# sch_CPU.net
KiCad netlist of a schematic drawn in Altium Designer
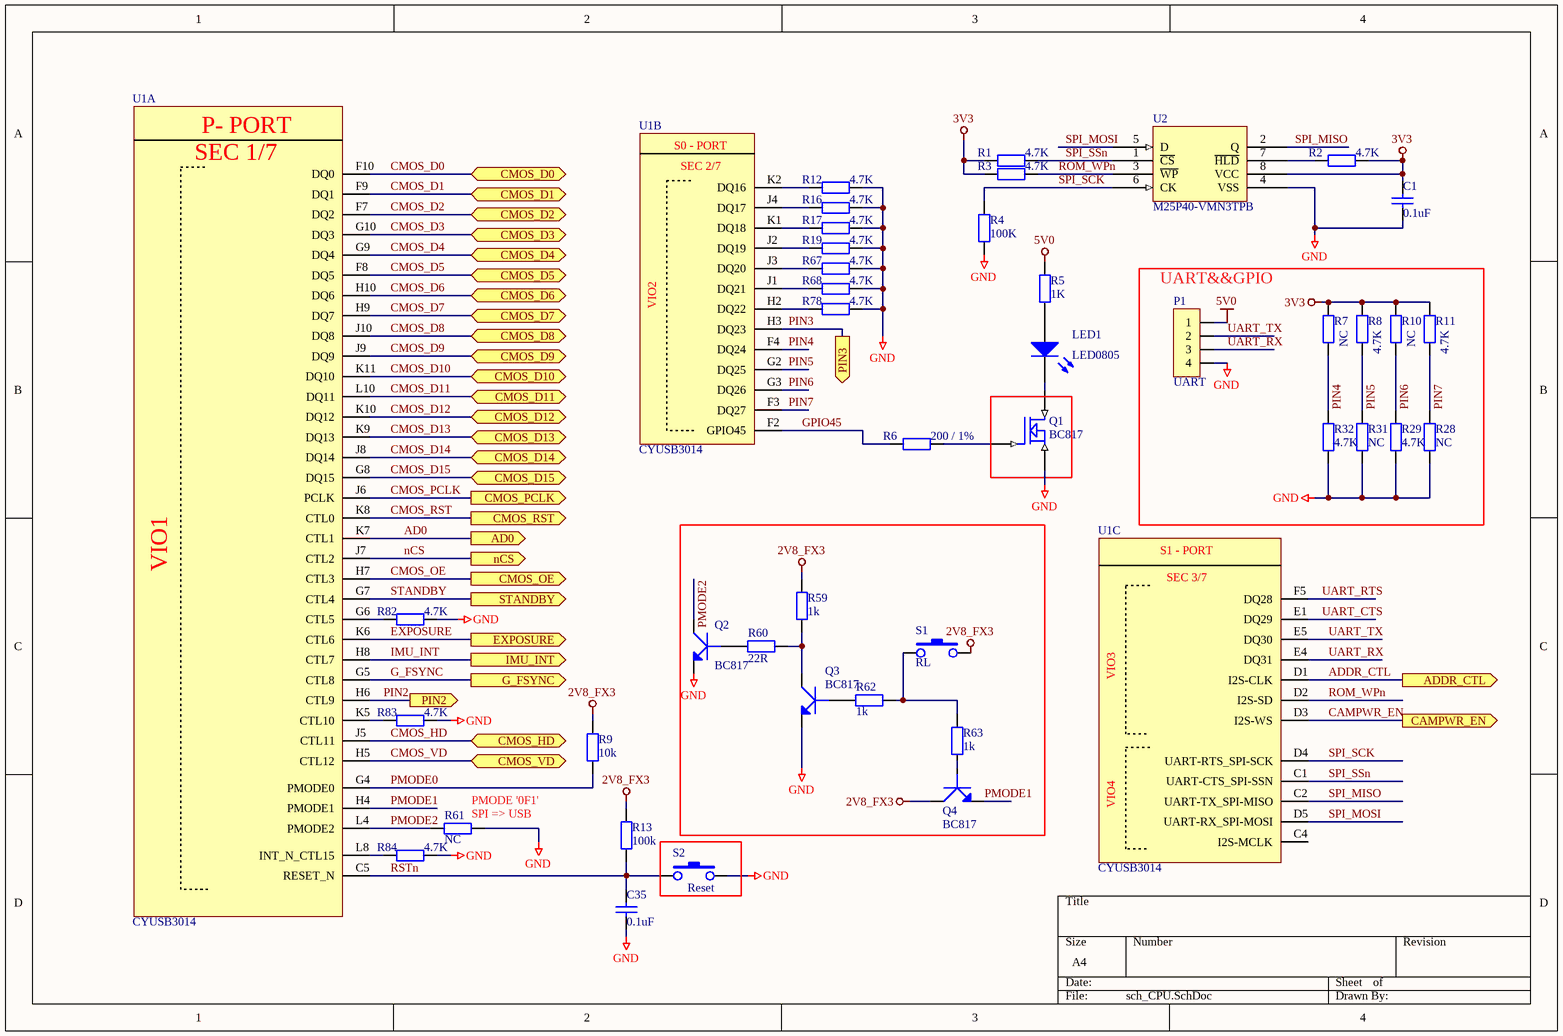
[diagram p0: sch_CPU.SchDoc]

(export (version "E")
  (design (tool "Eeschema 10.0.6"))
  (components
    (comp (ref "C1")
      (value "0.1uF")
      (footprint "0402C")
      (description "Capacitor")
      (fields (field (name "PUBLISHER") "Altium Limited"))
      (libsource (lib "Miscellaneous Devices") (part "Cap"))
    )
    (comp (ref "C35")
      (value "0.1uF")
      (footprint "0402C")
      (description "Capacitor")
      (fields (field (name "PUBLISHER") "Altium Limited"))
      (libsource (lib "Miscellaneous Devices") (part "Cap"))
    )
    (comp (ref "LED1")
      (value "LED0805")
      (footprint "LED0805A_L210W100H60")
      (description "发光二级管")
      (libsource (lib "TXW") (part "LED"))
    )
    (comp (ref "P1")
      (value "UART")
      (footprint "WAFER4_P1.25L6.25W3.4H4.3")
      (libsource (lib "KS_Drive") (part "CON4"))
    )
    (comp (ref "Q1")
      (value "BC817")
      (footprint "SOT-23L")
      (description "MOSFET N")
      (libsource (lib "TXW") (part "MOSFET N"))
    )
    (comp (ref "Q2")
      (value "BC817")
      (footprint "SOT-23L")
      (description "NPN Transistor")
      (libsource (lib "*") (part "NPN"))
    )
    (comp (ref "Q3")
      (value "BC817")
      (footprint "SOT-23L")
      (description "NPN Transistor")
      (libsource (lib "*") (part "NPN"))
    )
    (comp (ref "Q4")
      (value "BC817")
      (footprint "SOT-23L")
      (description "NPN Transistor")
      (libsource (lib "") (part "NPN_1"))
    )
    (comp (ref "R1")
      (value "4.7K")
      (footprint "0402R")
      (description "Resistor")
      (fields (field (name "PUBLISHER") "Altium Limited"))
      (libsource (lib "") (part "Resistor_2"))
    )
    (comp (ref "R2")
      (value "4.7K")
      (footprint "0402R")
      (description "Resistor")
      (fields (field (name "PUBLISHER") "Altium Limited"))
      (libsource (lib "") (part "Resistor_2"))
    )
    (comp (ref "R3")
      (value "4.7K")
      (footprint "0402R")
      (description "Resistor")
      (fields (field (name "PUBLISHER") "Altium Limited"))
      (libsource (lib "") (part "Resistor_2"))
    )
    (comp (ref "R4")
      (value "100K")
      (footprint "0402R")
      (description "Resistor")
      (fields (field (name "PUBLISHER") "Altium Limited"))
      (libsource (lib "") (part "Resistor_3"))
    )
    (comp (ref "R5")
      (value "1K")
      (footprint "0402R")
      (description "Resistor")
      (fields (field (name "PUBLISHER") "Altium Limited"))
      (libsource (lib "SZG") (part "Resistor"))
    )
    (comp (ref "R6")
      (value "200 / 1%")
      (footprint "0402R")
      (description "Resistor")
      (fields (field (name "Comment") "200R") (field (name "PUBLISHER") "Altium Limited"))
      (libsource (lib "") (part "Resistor_2"))
    )
    (comp (ref "R7")
      (value "NC")
      (footprint "0402R")
      (description "Resistor")
      (fields (field (name "PUBLISHER") "Altium Limited"))
      (libsource (lib "") (part "Resistor_3"))
    )
    (comp (ref "R8")
      (value "4.7K")
      (footprint "0402R")
      (description "Resistor")
      (fields (field (name "PUBLISHER") "Altium Limited"))
      (libsource (lib "") (part "Resistor_3"))
    )
    (comp (ref "R9")
      (value "10k")
      (footprint "0402R")
      (description "Resistor")
      (fields (field (name "Comment") "10K") (field (name "PUBLISHER") "Altium Limited"))
      (libsource (lib "SZG") (part "Resistor"))
    )
    (comp (ref "R10")
      (value "NC")
      (footprint "0402R")
      (description "Resistor")
      (fields (field (name "PUBLISHER") "Altium Limited"))
      (libsource (lib "") (part "Resistor_3"))
    )
    (comp (ref "R11")
      (value "4.7K")
      (footprint "0402R")
      (description "Resistor")
      (fields (field (name "PUBLISHER") "Altium Limited"))
      (libsource (lib "") (part "Resistor_3"))
    )
    (comp (ref "R12")
      (value "4.7K")
      (footprint "0402R")
      (description "Resistor")
      (fields (field (name "PUBLISHER") "Altium Limited"))
      (libsource (lib "") (part "Resistor_2"))
    )
    (comp (ref "R13")
      (value "100k")
      (footprint "0402R")
      (description "Resistor")
      (fields (field (name "Comment") "100K") (field (name "PUBLISHER") "Altium Limited"))
      (libsource (lib "SZG") (part "Resistor"))
    )
    (comp (ref "R16")
      (value "4.7K")
      (footprint "0402R")
      (description "Resistor")
      (fields (field (name "PUBLISHER") "Altium Limited"))
      (libsource (lib "") (part "Resistor_2"))
    )
    (comp (ref "R17")
      (value "4.7K")
      (footprint "0402R")
      (description "Resistor")
      (fields (field (name "PUBLISHER") "Altium Limited"))
      (libsource (lib "") (part "Resistor_2"))
    )
    (comp (ref "R19")
      (value "4.7K")
      (footprint "0402R")
      (description "Resistor")
      (fields (field (name "PUBLISHER") "Altium Limited"))
      (libsource (lib "") (part "Resistor_2"))
    )
    (comp (ref "R28")
      (value "NC")
      (footprint "0402R")
      (description "Resistor")
      (fields (field (name "PUBLISHER") "Altium Limited"))
      (libsource (lib "SZG") (part "Resistor"))
    )
    (comp (ref "R29")
      (value "4.7K")
      (footprint "0402R")
      (description "Resistor")
      (fields (field (name "PUBLISHER") "Altium Limited"))
      (libsource (lib "SZG") (part "Resistor"))
    )
    (comp (ref "R31")
      (value "NC")
      (footprint "0402R")
      (description "Resistor")
      (fields (field (name "Comment") "N~{C}") (field (name "PUBLISHER") "Altium Limited"))
      (libsource (lib "SZG") (part "Resistor"))
    )
    (comp (ref "R32")
      (value "4.7K")
      (footprint "0402R")
      (description "Resistor")
      (fields (field (name "PUBLISHER") "Altium Limited"))
      (libsource (lib "SZG") (part "Resistor"))
    )
    (comp (ref "R59")
      (value "1k")
      (footprint "0402R")
      (description "Resistor")
      (fields (field (name "Comment") "1K") (field (name "PUBLISHER") "Altium Limited"))
      (libsource (lib "") (part "Resistor_3"))
    )
    (comp (ref "R60")
      (value "22R")
      (footprint "0402R")
      (description "Resistor")
      (fields (field (name "PUBLISHER") "Altium Limited"))
      (libsource (lib "") (part "Resistor_2"))
    )
    (comp (ref "R61")
      (value "NC")
      (footprint "0805R")
      (description "Resistor")
      (fields (field (name "PUBLISHER") "Altium Limited"))
      (libsource (lib "") (part "Resistor_1"))
    )
    (comp (ref "R62")
      (value "1k")
      (footprint "0402R")
      (description "Resistor")
      (fields (field (name "PUBLISHER") "Altium Limited"))
      (libsource (lib "") (part "Resistor_1"))
    )
    (comp (ref "R63")
      (value "1k")
      (footprint "0402R")
      (description "Resistor")
      (fields (field (name "PUBLISHER") "Altium Limited"))
      (libsource (lib "SZG") (part "Resistor"))
    )
    (comp (ref "R67")
      (value "4.7K")
      (footprint "0402R")
      (description "Resistor")
      (fields (field (name "PUBLISHER") "Altium Limited"))
      (libsource (lib "") (part "Resistor_2"))
    )
    (comp (ref "R68")
      (value "4.7K")
      (footprint "0402R")
      (description "Resistor")
      (fields (field (name "PUBLISHER") "Altium Limited"))
      (libsource (lib "") (part "Resistor_2"))
    )
    (comp (ref "R78")
      (value "4.7K")
      (footprint "0402R")
      (description "Resistor")
      (fields (field (name "PUBLISHER") "Altium Limited"))
      (libsource (lib "") (part "Resistor_2"))
    )
    (comp (ref "R82")
      (value "4.7K")
      (footprint "0402R")
      (description "Resistor")
      (fields (field (name "PUBLISHER") "Altium Limited"))
      (libsource (lib "") (part "Resistor_2"))
    )
    (comp (ref "R83")
      (value "4.7K")
      (footprint "0402R")
      (description "Resistor")
      (fields (field (name "PUBLISHER") "Altium Limited"))
      (libsource (lib "") (part "Resistor_2"))
    )
    (comp (ref "R84")
      (value "4.7K")
      (footprint "0402R")
      (description "Resistor")
      (fields (field (name "PUBLISHER") "Altium Limited"))
      (libsource (lib "") (part "Resistor_2"))
    )
    (comp (ref "S1")
      (value "RL")
      (footprint "SW_L40W30H25_MPTFP")
      (description "Button_sop")
      (libsource (lib "SZG") (part "Button_sop"))
    )
    (comp (ref "S2")
      (value "Reset")
      (footprint "SW_L40W30H25_MPTFP")
      (description "Button_sop")
      (libsource (lib "SZG") (part "Button_sop"))
    )
    (comp (ref "U1")
      (value "CYUSB3014")
      (footprint "FBGA121_P80L100W100H11")
      (libsource (lib "TXW") (part "CYUSB3014"))
    )
    (comp (ref "U2")
      (value "M25P40-VMN3TPB")
      (footprint "SO8N_P127L50W40W62H17")
      (libsource (lib "TXW") (part "M25P40-VMN3TPB"))
    )
  )
  (nets
    (net (code "1") (name "/AD0") (class "Default")
      (node (ref "U1") (pin "K7") (pinfunction "CTL1_K7") (pintype "passive"))
    )
    (net (code "2") (name "/ADDR_CTL") (class "Default")
      (node (ref "U1") (pin "D1") (pinfunction "I2S-CLK_D1") (pintype "passive"))
    )
    (net (code "3") (name "/CAMPWR_EN") (class "Default")
      (node (ref "U1") (pin "D3") (pinfunction "I2S-WS_D3") (pintype "passive"))
    )
    (net (code "4") (name "/CMOS_D0") (class "Default")
      (node (ref "U1") (pin "F10") (pinfunction "DQ0_F10") (pintype "passive"))
    )
    (net (code "5") (name "/CMOS_D1") (class "Default")
      (node (ref "U1") (pin "F9") (pinfunction "DQ1_F9") (pintype "passive"))
    )
    (net (code "6") (name "/CMOS_D2") (class "Default")
      (node (ref "U1") (pin "F7") (pinfunction "DQ2_F7") (pintype "passive"))
    )
    (net (code "7") (name "/CMOS_D3") (class "Default")
      (node (ref "U1") (pin "G10") (pinfunction "DQ3_G10") (pintype "passive"))
    )
    (net (code "8") (name "/CMOS_D4") (class "Default")
      (node (ref "U1") (pin "G9") (pinfunction "DQ4_G9") (pintype "passive"))
    )
    (net (code "9") (name "/CMOS_D5") (class "Default")
      (node (ref "U1") (pin "F8") (pinfunction "DQ5_F8") (pintype "passive"))
    )
    (net (code "10") (name "/CMOS_D6") (class "Default")
      (node (ref "U1") (pin "H10") (pinfunction "DQ6_H10") (pintype "passive"))
    )
    (net (code "11") (name "/CMOS_D7") (class "Default")
      (node (ref "U1") (pin "H9") (pinfunction "DQ7_H9") (pintype "passive"))
    )
    (net (code "12") (name "/CMOS_D8") (class "Default")
      (node (ref "U1") (pin "J10") (pinfunction "DQ8_J10") (pintype "passive"))
    )
    (net (code "13") (name "/CMOS_D9") (class "Default")
      (node (ref "U1") (pin "J9") (pinfunction "DQ9_J9") (pintype "passive"))
    )
    (net (code "14") (name "/CMOS_D10") (class "Default")
      (node (ref "U1") (pin "K11") (pinfunction "DQ10_K11") (pintype "passive"))
    )
    (net (code "15") (name "/CMOS_D11") (class "Default")
      (node (ref "U1") (pin "L10") (pinfunction "DQ11_L10") (pintype "passive"))
    )
    (net (code "16") (name "/CMOS_D12") (class "Default")
      (node (ref "U1") (pin "K10") (pinfunction "DQ12_K10") (pintype "passive"))
    )
    (net (code "17") (name "/CMOS_D13") (class "Default")
      (node (ref "U1") (pin "K9") (pinfunction "DQ13_K9") (pintype "passive"))
    )
    (net (code "18") (name "/CMOS_D14") (class "Default")
      (node (ref "U1") (pin "J8") (pinfunction "DQ14_J8") (pintype "passive"))
    )
    (net (code "19") (name "/CMOS_D15") (class "Default")
      (node (ref "U1") (pin "G8") (pinfunction "DQ15_G8") (pintype "passive"))
    )
    (net (code "20") (name "/CMOS_HD") (class "Default")
      (node (ref "U1") (pin "J5") (pinfunction "CTL11_J5") (pintype "passive"))
    )
    (net (code "21") (name "/CMOS_OE") (class "Default")
      (node (ref "U1") (pin "H7") (pinfunction "CTL3_H7") (pintype "passive"))
    )
    (net (code "22") (name "/CMOS_PCLK") (class "Default")
      (node (ref "U1") (pin "J6") (pinfunction "PCLK_J6") (pintype "passive"))
    )
    (net (code "23") (name "/CMOS_RST") (class "Default")
      (node (ref "U1") (pin "K8") (pinfunction "CTL0_K8") (pintype "passive"))
    )
    (net (code "24") (name "/CMOS_VD") (class "Default")
      (node (ref "U1") (pin "H5") (pinfunction "CTL12_H5") (pintype "passive"))
    )
    (net (code "25") (name "/EXPOSURE") (class "Default")
      (node (ref "U1") (pin "K6") (pinfunction "CTL6_K6") (pintype "passive"))
    )
    (net (code "26") (name "/GPIO45") (class "Default")
      (node (ref "R6") (pin "1") (pinfunction "1_1") (pintype "passive"))
      (node (ref "U1") (pin "F2") (pinfunction "GPIO45_F2") (pintype "passive"))
    )
    (net (code "27") (name "/G_FSYNC") (class "Default")
      (node (ref "U1") (pin "G5") (pinfunction "CTL8_G5") (pintype "passive"))
    )
    (net (code "28") (name "/IMU_INT") (class "Default")
      (node (ref "U1") (pin "H8") (pinfunction "CTL7_H8") (pintype "passive"))
    )
    (net (code "29") (name "/PIN2") (class "Default")
      (node (ref "U1") (pin "H6") (pinfunction "CTL9_H6") (pintype "passive"))
    )
    (net (code "30") (name "/PIN3") (class "Default")
      (node (ref "U1") (pin "H3") (pinfunction "DQ23_H3") (pintype "passive"))
    )
    (net (code "31") (name "/PIN4") (class "Default")
      (node (ref "R32") (pin "1") (pinfunction "1_1") (pintype "passive"))
      (node (ref "R7") (pin "1") (pinfunction "1_1") (pintype "passive"))
      (node (ref "U1") (pin "F4") (pinfunction "DQ24_F4") (pintype "passive"))
    )
    (net (code "32") (name "/PIN5") (class "Default")
      (node (ref "R31") (pin "1") (pinfunction "1_1") (pintype "passive"))
      (node (ref "R8") (pin "1") (pinfunction "1_1") (pintype "passive"))
      (node (ref "U1") (pin "G2") (pinfunction "DQ25_G2") (pintype "passive"))
    )
    (net (code "33") (name "/PIN6") (class "Default")
      (node (ref "R10") (pin "1") (pinfunction "1_1") (pintype "passive"))
      (node (ref "R29") (pin "1") (pinfunction "1_1") (pintype "passive"))
      (node (ref "U1") (pin "G3") (pinfunction "DQ26_G3") (pintype "passive"))
    )
    (net (code "34") (name "/PIN7") (class "Default")
      (node (ref "R11") (pin "1") (pinfunction "1_1") (pintype "passive"))
      (node (ref "R28") (pin "1") (pinfunction "1_1") (pintype "passive"))
      (node (ref "U1") (pin "F3") (pinfunction "DQ27_F3") (pintype "passive"))
    )
    (net (code "35") (name "/PMODE0") (class "Default")
      (node (ref "R9") (pin "2") (pinfunction "2_2") (pintype "passive"))
      (node (ref "U1") (pin "G4") (pinfunction "PMODE0_G4") (pintype "passive"))
    )
    (net (code "36") (name "/PMODE1") (class "Default")
      (node (ref "Q4") (pin "2") (pinfunction "E_2") (pintype "passive"))
      (node (ref "U1") (pin "H4") (pinfunction "PMODE1_H4") (pintype "passive"))
    )
    (net (code "37") (name "/PMODE2") (class "Default")
      (node (ref "Q2") (pin "3") (pinfunction "C_3") (pintype "passive"))
      (node (ref "R61") (pin "2") (pinfunction "2_2") (pintype "passive"))
      (node (ref "U1") (pin "L4") (pinfunction "PMODE2_L4") (pintype "passive"))
    )
    (net (code "38") (name "/ROM_WPn") (class "Default")
      (node (ref "R3") (pin "2") (pinfunction "2_2") (pintype "passive"))
      (node (ref "U1") (pin "D2") (pinfunction "I2S-SD_D2") (pintype "passive"))
      (node (ref "U2") (pin "3") (pinfunction "~{WP}_3") (pintype "passive"))
    )
    (net (code "39") (name "/RSTn") (class "Default")
      (node (ref "C35") (pin "2") (pinfunction "2_2") (pintype "passive"))
      (node (ref "R13") (pin "2") (pinfunction "2_2") (pintype "passive"))
      (node (ref "S2") (pin "1") (pinfunction "1_1") (pintype "passive"))
      (node (ref "U1") (pin "C5") (pinfunction "RESET_N_C5") (pintype "passive"))
    )
    (net (code "40") (name "/SPI_MISO") (class "Default")
      (node (ref "U1") (pin "C2") (pinfunction "UART-TX_SPI-MISO_C2") (pintype "passive"))
      (node (ref "U2") (pin "2") (pinfunction "Q_2") (pintype "passive"))
    )
    (net (code "41") (name "/SPI_MOSI") (class "Default")
      (node (ref "U1") (pin "D5") (pinfunction "UART-RX_SPI-MOSI_D5") (pintype "passive"))
      (node (ref "U2") (pin "5") (pinfunction "D_5") (pintype "input"))
    )
    (net (code "42") (name "/SPI_SCK") (class "Default")
      (node (ref "R4") (pin "2") (pinfunction "2_2") (pintype "passive"))
      (node (ref "U1") (pin "D4") (pinfunction "UART-RTS_SPI-SCK_D4") (pintype "passive"))
      (node (ref "U2") (pin "6") (pinfunction "CK_6") (pintype "input"))
    )
    (net (code "43") (name "/SPI_SSn") (class "Default")
      (node (ref "R1") (pin "2") (pinfunction "2_2") (pintype "passive"))
      (node (ref "U1") (pin "C1") (pinfunction "UART-CTS_SPI-SSN_C1") (pintype "passive"))
      (node (ref "U2") (pin "1") (pinfunction "~{CS}_1") (pintype "passive"))
    )
    (net (code "44") (name "/STANDBY") (class "Default")
      (node (ref "U1") (pin "G7") (pinfunction "CTL4_G7") (pintype "passive"))
    )
    (net (code "45") (name "/UART_CTS") (class "Default")
      (node (ref "U1") (pin "E1") (pinfunction "DQ29_E1") (pintype "passive"))
    )
    (net (code "46") (name "/UART_RTS") (class "Default")
      (node (ref "U1") (pin "F5") (pinfunction "DQ28_F5") (pintype "passive"))
    )
    (net (code "47") (name "/UART_RX") (class "Default")
      (node (ref "P1") (pin "3") (pinfunction "3_3") (pintype "passive"))
      (node (ref "U1") (pin "E4") (pinfunction "DQ31_E4") (pintype "passive"))
    )
    (net (code "48") (name "/UART_TX") (class "Default")
      (node (ref "P1") (pin "2") (pinfunction "2_2") (pintype "passive"))
      (node (ref "U1") (pin "E5") (pinfunction "DQ30_E5") (pintype "passive"))
    )
    (net (code "49") (name "/nCS") (class "Default")
      (node (ref "U1") (pin "J7") (pinfunction "CTL2_J7") (pintype "passive"))
    )
    (net (code "50") (name "2V8_FX3") (class "Default")
      (node (ref "Q4") (pin "3") (pinfunction "C_3") (pintype "passive"))
      (node (ref "R13") (pin "1") (pinfunction "1_1") (pintype "passive"))
      (node (ref "R59") (pin "2") (pinfunction "2_2") (pintype "passive"))
      (node (ref "R9") (pin "1") (pinfunction "1_1") (pintype "passive"))
      (node (ref "S1") (pin "1") (pinfunction "1_1") (pintype "passive"))
    )
    (net (code "51") (name "3V3") (class "Default")
      (node (ref "C1") (pin "2") (pinfunction "2_2") (pintype "passive"))
      (node (ref "R1") (pin "1") (pinfunction "1_1") (pintype "passive"))
      (node (ref "R10") (pin "2") (pinfunction "2_2") (pintype "passive"))
      (node (ref "R11") (pin "2") (pinfunction "2_2") (pintype "passive"))
      (node (ref "R2") (pin "2") (pinfunction "2_2") (pintype "passive"))
      (node (ref "R3") (pin "1") (pinfunction "1_1") (pintype "passive"))
      (node (ref "R7") (pin "2") (pinfunction "2_2") (pintype "passive"))
      (node (ref "R8") (pin "2") (pinfunction "2_2") (pintype "passive"))
      (node (ref "U2") (pin "8") (pinfunction "VCC_8") (pintype "passive"))
    )
    (net (code "52") (name "5V0") (class "Default")
      (node (ref "P1") (pin "1") (pinfunction "1_1") (pintype "passive"))
      (node (ref "R5") (pin "1") (pinfunction "1_1") (pintype "passive"))
    )
    (net (code "53") (name "GND") (class "Default")
      (node (ref "C1") (pin "1") (pinfunction "1_1") (pintype "passive"))
      (node (ref "C35") (pin "1") (pinfunction "1_1") (pintype "passive"))
      (node (ref "P1") (pin "4") (pinfunction "4_4") (pintype "passive"))
      (node (ref "Q1") (pin "2") (pinfunction "S_2") (pintype "input"))
      (node (ref "Q2") (pin "2") (pinfunction "E_2") (pintype "passive"))
      (node (ref "Q3") (pin "2") (pinfunction "E_2") (pintype "passive"))
      (node (ref "R12") (pin "2") (pinfunction "2_2") (pintype "passive"))
      (node (ref "R16") (pin "2") (pinfunction "2_2") (pintype "passive"))
      (node (ref "R17") (pin "2") (pinfunction "2_2") (pintype "passive"))
      (node (ref "R19") (pin "2") (pinfunction "2_2") (pintype "passive"))
      (node (ref "R28") (pin "2") (pinfunction "2_2") (pintype "passive"))
      (node (ref "R29") (pin "2") (pinfunction "2_2") (pintype "passive"))
      (node (ref "R31") (pin "2") (pinfunction "2_2") (pintype "passive"))
      (node (ref "R32") (pin "2") (pinfunction "2_2") (pintype "passive"))
      (node (ref "R4") (pin "1") (pinfunction "1_1") (pintype "passive"))
      (node (ref "R61") (pin "1") (pinfunction "1_1") (pintype "passive"))
      (node (ref "R67") (pin "2") (pinfunction "2_2") (pintype "passive"))
      (node (ref "R68") (pin "2") (pinfunction "2_2") (pintype "passive"))
      (node (ref "R78") (pin "2") (pinfunction "2_2") (pintype "passive"))
      (node (ref "R82") (pin "2") (pinfunction "2_2") (pintype "passive"))
      (node (ref "R83") (pin "2") (pinfunction "2_2") (pintype "passive"))
      (node (ref "R84") (pin "2") (pinfunction "2_2") (pintype "passive"))
      (node (ref "S2") (pin "2") (pinfunction "2_2") (pintype "passive"))
      (node (ref "U2") (pin "4") (pinfunction "VSS_4") (pintype "passive"))
    )
    (net (code "54") (name "Net-(LED1-A)") (class "Default")
      (node (ref "LED1") (pin "1") (pinfunction "A_1") (pintype "passive"))
      (node (ref "R5") (pin "2") (pinfunction "2_2") (pintype "passive"))
    )
    (net (code "55") (name "Net-(LED1-K)") (class "Default")
      (node (ref "LED1") (pin "2") (pinfunction "K_2") (pintype "passive"))
      (node (ref "Q1") (pin "3") (pinfunction "D_3") (pintype "input"))
    )
    (net (code "56") (name "Net-(Q1-G)") (class "Default")
      (node (ref "Q1") (pin "1") (pinfunction "G_1") (pintype "input"))
      (node (ref "R6") (pin "2") (pinfunction "2_2") (pintype "passive"))
    )
    (net (code "57") (name "Net-(Q2-B)") (class "Default")
      (node (ref "Q2") (pin "1") (pinfunction "B_1") (pintype "passive"))
      (node (ref "R60") (pin "1") (pinfunction "1_1") (pintype "passive"))
    )
    (net (code "58") (name "Net-(Q3-B)") (class "Default")
      (node (ref "Q3") (pin "1") (pinfunction "B_1") (pintype "passive"))
      (node (ref "R62") (pin "2") (pinfunction "2_2") (pintype "passive"))
    )
    (net (code "59") (name "Net-(Q3-C)") (class "Default")
      (node (ref "Q3") (pin "3") (pinfunction "C_3") (pintype "passive"))
      (node (ref "R59") (pin "1") (pinfunction "1_1") (pintype "passive"))
      (node (ref "R60") (pin "2") (pinfunction "2_2") (pintype "passive"))
    )
    (net (code "60") (name "Net-(Q4-B)") (class "Default")
      (node (ref "Q4") (pin "1") (pinfunction "B_1") (pintype "passive"))
      (node (ref "R63") (pin "2") (pinfunction "2_2") (pintype "passive"))
    )
    (net (code "61") (name "Net-(R62-Pad1)") (class "Default")
      (node (ref "R62") (pin "1") (pinfunction "1_1") (pintype "passive"))
      (node (ref "R63") (pin "1") (pinfunction "1_1") (pintype "passive"))
      (node (ref "S1") (pin "2") (pinfunction "2_2") (pintype "passive"))
    )
    (net (code "62") (name "Net-(U1A-CTL5)") (class "Default")
      (node (ref "R82") (pin "1") (pinfunction "1_1") (pintype "passive"))
      (node (ref "U1") (pin "G6") (pinfunction "CTL5_G6") (pintype "passive"))
    )
    (net (code "63") (name "Net-(U1A-CTL10)") (class "Default")
      (node (ref "R83") (pin "1") (pinfunction "1_1") (pintype "passive"))
      (node (ref "U1") (pin "K5") (pinfunction "CTL10_K5") (pintype "passive"))
    )
    (net (code "64") (name "Net-(U1A-INT_N_CTL15)") (class "Default")
      (node (ref "R84") (pin "1") (pinfunction "1_1") (pintype "passive"))
      (node (ref "U1") (pin "L8") (pinfunction "INT_N_CTL15_L8") (pintype "passive"))
    )
    (net (code "65") (name "Net-(U1B-DQ16)") (class "Default")
      (node (ref "R12") (pin "1") (pinfunction "1_1") (pintype "passive"))
      (node (ref "U1") (pin "K2") (pinfunction "DQ16_K2") (pintype "passive"))
    )
    (net (code "66") (name "Net-(U1B-DQ17)") (class "Default")
      (node (ref "R16") (pin "1") (pinfunction "1_1") (pintype "passive"))
      (node (ref "U1") (pin "J4") (pinfunction "DQ17_J4") (pintype "passive"))
    )
    (net (code "67") (name "Net-(U1B-DQ18)") (class "Default")
      (node (ref "R17") (pin "1") (pinfunction "1_1") (pintype "passive"))
      (node (ref "U1") (pin "K1") (pinfunction "DQ18_K1") (pintype "passive"))
    )
    (net (code "68") (name "Net-(U1B-DQ19)") (class "Default")
      (node (ref "R19") (pin "1") (pinfunction "1_1") (pintype "passive"))
      (node (ref "U1") (pin "J2") (pinfunction "DQ19_J2") (pintype "passive"))
    )
    (net (code "69") (name "Net-(U1B-DQ20)") (class "Default")
      (node (ref "R67") (pin "1") (pinfunction "1_1") (pintype "passive"))
      (node (ref "U1") (pin "J3") (pinfunction "DQ20_J3") (pintype "passive"))
    )
    (net (code "70") (name "Net-(U1B-DQ21)") (class "Default")
      (node (ref "R68") (pin "1") (pinfunction "1_1") (pintype "passive"))
      (node (ref "U1") (pin "J1") (pinfunction "DQ21_J1") (pintype "passive"))
    )
    (net (code "71") (name "Net-(U1B-DQ22)") (class "Default")
      (node (ref "R78") (pin "1") (pinfunction "1_1") (pintype "passive"))
      (node (ref "U1") (pin "H2") (pinfunction "DQ22_H2") (pintype "passive"))
    )
    (net (code "72") (name "Net-(U2-~{HLD})") (class "Default")
      (node (ref "R2") (pin "1") (pinfunction "1_1") (pintype "passive"))
      (node (ref "U2") (pin "7") (pinfunction "~{HLD}_7") (pintype "passive"))
    )
    (net (code "73") (name "unconnected-(U1C-I2S-MCLK-PadC4)") (class "Default")
      (node (ref "U1") (pin "C4") (pinfunction "I2S-MCLK_C4") (pintype "passive"))
    )
  )
)
